# esp32-board.net
KiCad netlist of a schematic drawn in EasyEDA Pro
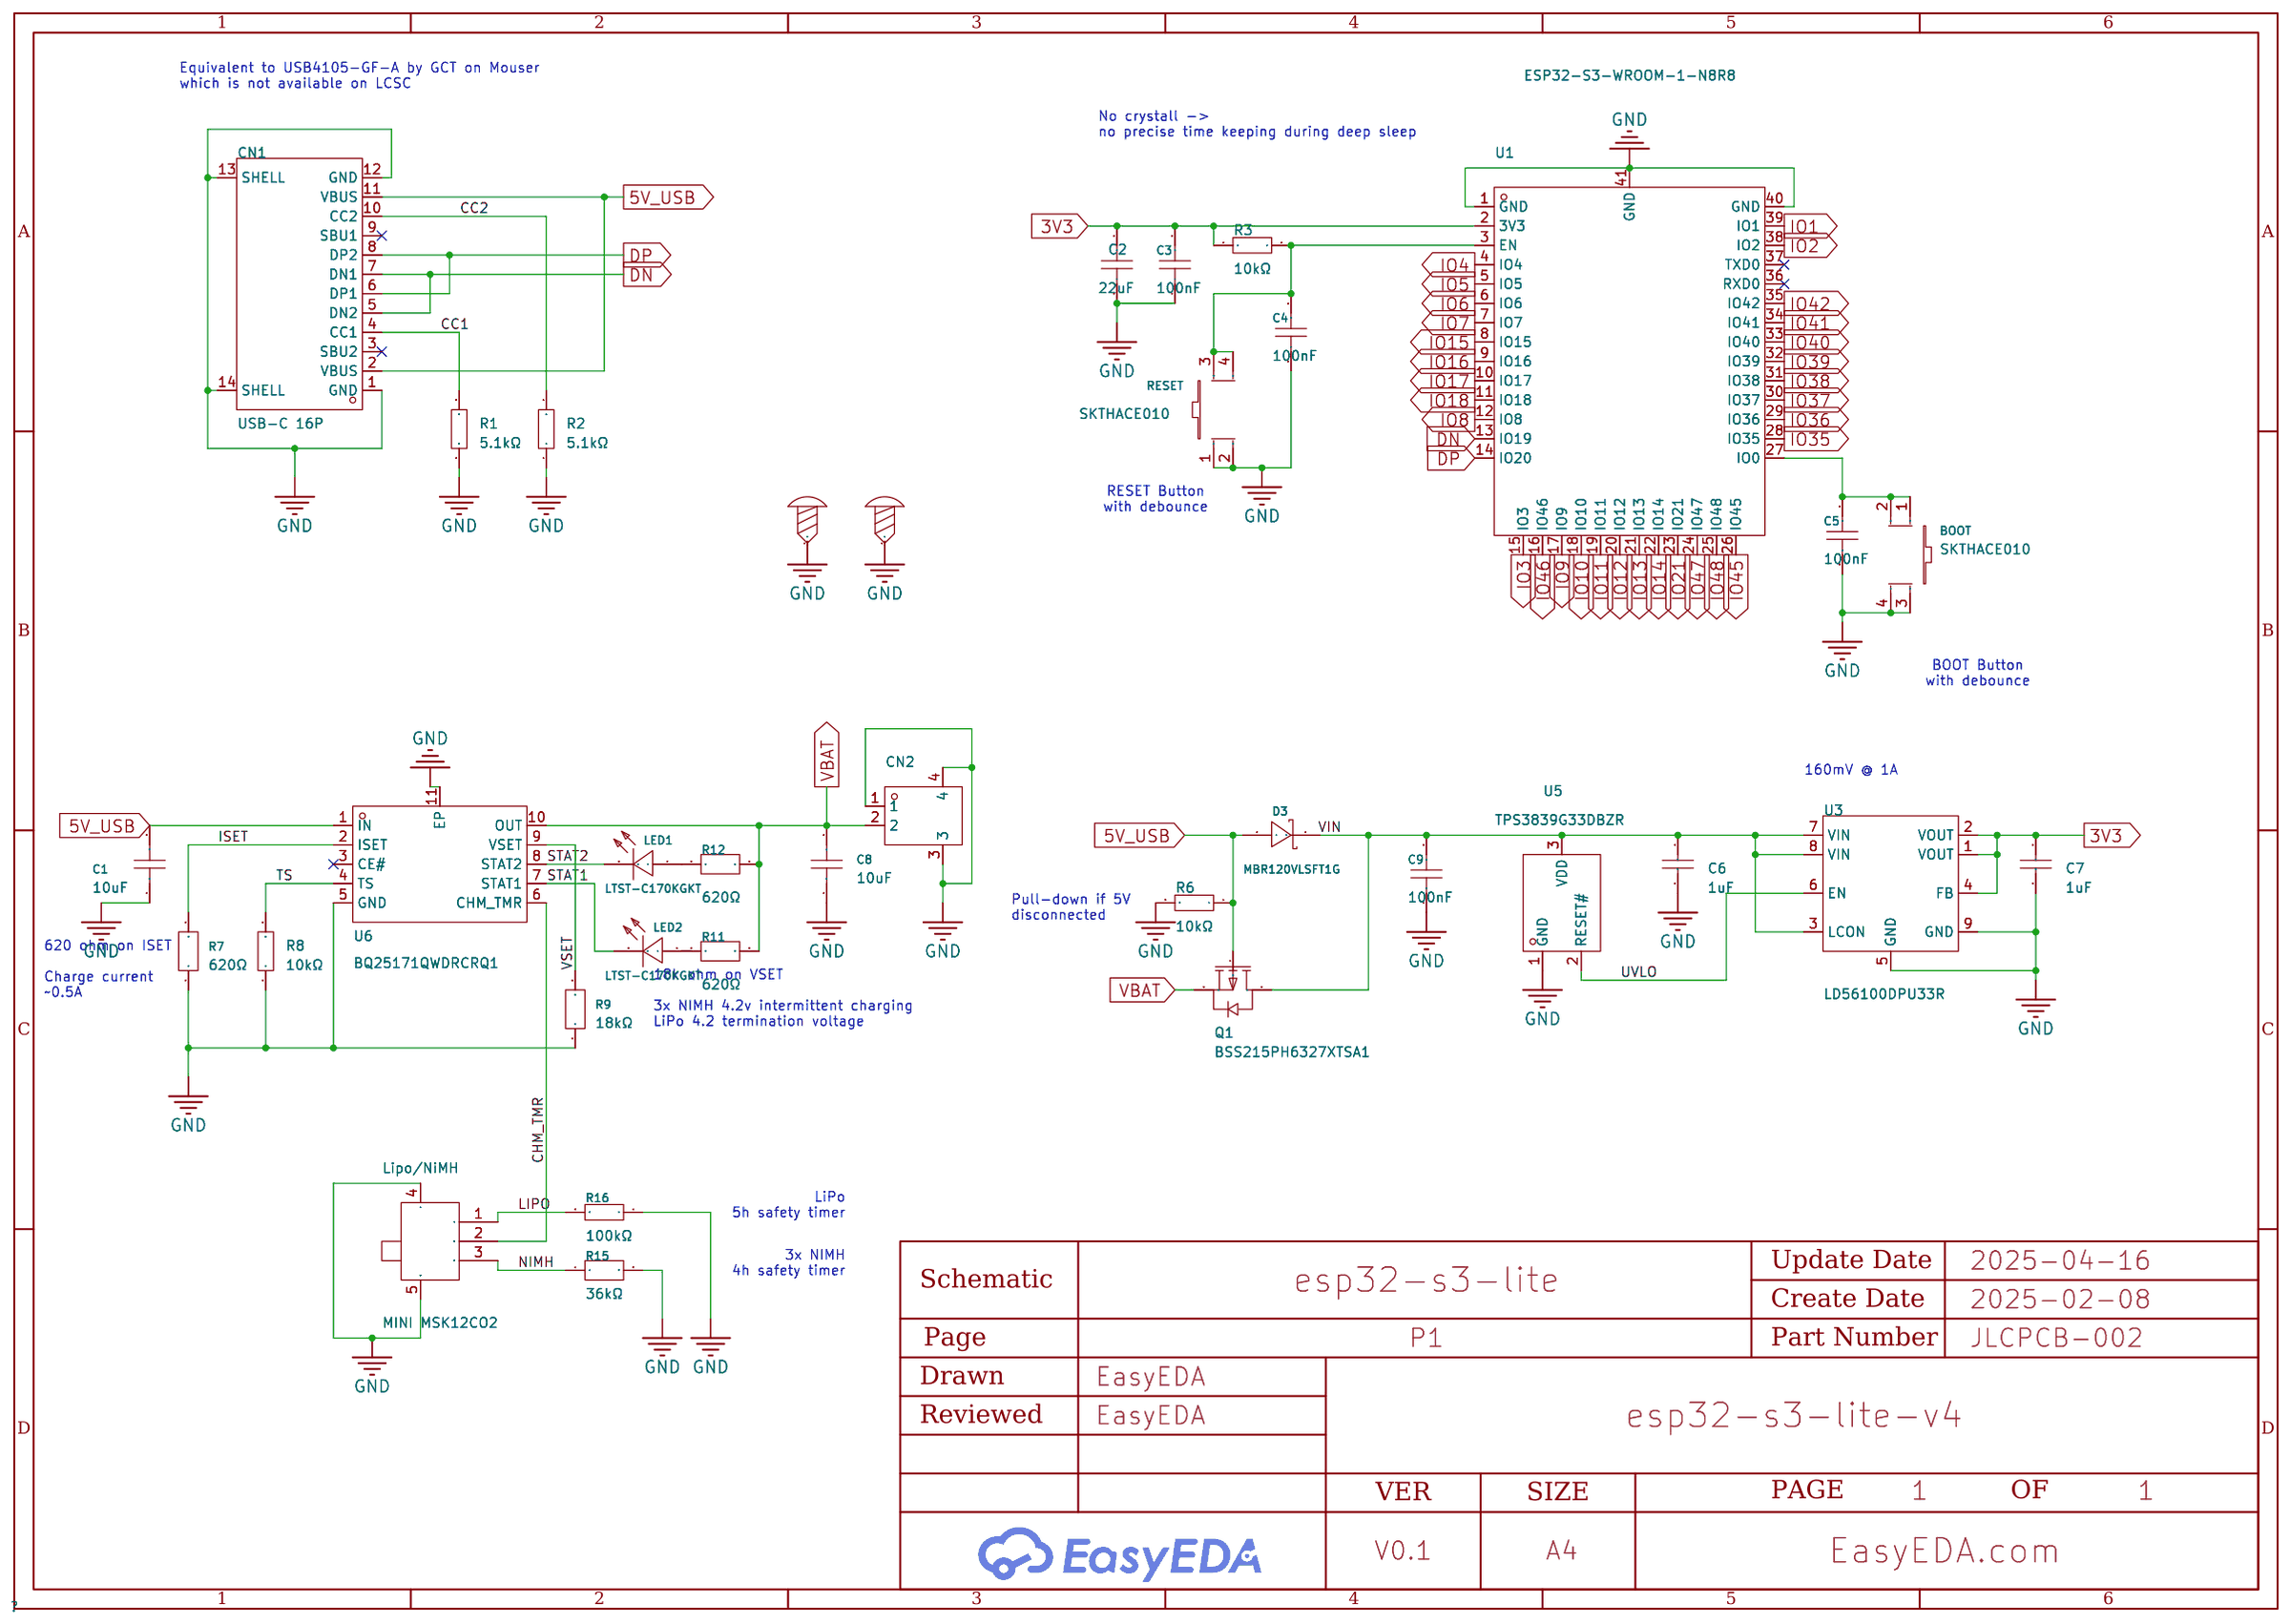
[diagram p0: schematic sheet]

(export (version "E")
  (design (tool "Eeschema 10.0.6"))
  (components
    (comp (ref "BOOT")
      (value "SKTHACE010")
      (footprint "easyedapro:KEY-SMD_4P-L3.5-W3.2-P1.50-LS3.60")
      (fields (field (name "Manufacturer") "ALPSALPINE(阿尔卑斯阿尔派)"))
      (libsource (lib "easyedapro") (part "SKTHACE010"))
    )
    (comp (ref "C1")
      (value "10uF")
      (footprint "easyedapro:C0603")
      (fields
        (field (name "Manufacturer Part") "CL10A106MA8NRNC")
        (field (name "Manufacturer") "SAMSUNG(三星)")
      )
      (libsource (lib "easyedapro") (part "CL10A106MA8NRNC"))
    )
    (comp (ref "C2")
      (value "22uF")
      (footprint "easyedapro:C0603")
      (fields
        (field (name "Manufacturer Part") "CL10A226MP8NUNE")
        (field (name "Manufacturer") "SAMSUNG(三星)")
      )
      (libsource (lib "easyedapro") (part "CL10A226MP8NUNE"))
    )
    (comp (ref "C3")
      (value "100nF")
      (footprint "easyedapro:C0603")
      (fields
        (field (name "Manufacturer Part") "CL10B104KB8NNNC")
        (field (name "Manufacturer") "SAMSUNG(三星)")
      )
      (libsource (lib "easyedapro") (part "CL10B104KB8NNNC"))
    )
    (comp (ref "C4")
      (value "100nF")
      (footprint "easyedapro:C0603")
      (fields
        (field (name "Manufacturer Part") "CL10B104KB8NNNC")
        (field (name "Manufacturer") "SAMSUNG(三星)")
      )
      (libsource (lib "easyedapro") (part "CL10B104KB8NNNC"))
    )
    (comp (ref "C5")
      (value "100nF")
      (footprint "easyedapro:C0603")
      (fields
        (field (name "Manufacturer Part") "CL10B104KB8NNNC")
        (field (name "Manufacturer") "SAMSUNG(三星)")
      )
      (libsource (lib "easyedapro") (part "CL10B104KB8NNNC"))
    )
    (comp (ref "C6")
      (value "1uF")
      (footprint "easyedapro:C0603")
      (fields
        (field (name "Manufacturer Part") "CL10A105KA8NNNC")
        (field (name "Manufacturer") "SAMSUNG(三星)")
      )
      (libsource (lib "easyedapro") (part "CL10A105KA8NNNC"))
    )
    (comp (ref "C7")
      (value "1uF")
      (footprint "easyedapro:C0603")
      (fields
        (field (name "Manufacturer Part") "CL10A105KA8NNNC")
        (field (name "Manufacturer") "SAMSUNG(三星)")
      )
      (libsource (lib "easyedapro") (part "CL10A105KA8NNNC"))
    )
    (comp (ref "C8")
      (value "10uF")
      (footprint "easyedapro:C0603")
      (fields
        (field (name "Manufacturer Part") "CL10A106MA8NRNC")
        (field (name "Manufacturer") "SAMSUNG(三星)")
      )
      (libsource (lib "easyedapro") (part "CL10A106MA8NRNC"))
    )
    (comp (ref "C9")
      (value "100nF")
      (footprint "easyedapro:C0603")
      (fields
        (field (name "Manufacturer Part") "CL10B104KB8NNNC")
        (field (name "Manufacturer") "SAMSUNG(三星)")
      )
      (libsource (lib "easyedapro") (part "CL10B104KB8NNNC"))
    )
    (comp (ref "CN1")
      (value "USB-C 16P")
      (footprint "easyedapro:USB-C-SMD_TYPE-C-6PIN-2MD-073")
      (fields
        (field (name "Manufacturer Part") "TYPE-C 16PIN 2MD(073)")
        (field (name "Manufacturer") "SHOU HAN(首韩)")
      )
      (libsource (lib "easyedapro") (part "TYPE-C 16PIN 2MD(073)"))
    )
    (comp (ref "CN2")
      (value "B2B-PH-SM4-TB(LF)(SN)")
      (footprint "easyedapro:CONN-SMD_B2B-PH-SM4-TB-LF-SN")
      (fields (field (name "Manufacturer") "JST"))
      (libsource (lib "easyedapro") (part "B2B-PH-SM4-TB (LF)(SN)"))
    )
    (comp (ref "D3")
      (value "MBR120VLSFT1G")
      (footprint "easyedapro:SOD-123F_L2.8-W1.8-LS3.7-RD")
      (fields (field (name "Manufacturer") "onsemi(安森美)"))
      (libsource (lib "easyedapro") (part "MBR120VLSFT1G"))
    )
    (comp (ref "LED1")
      (value "LTST-C170KGKT")
      (footprint "easyedapro:LED0805-R-RD")
      (fields (field (name "Manufacturer") "LITEON(光宝)"))
      (libsource (lib "easyedapro") (part "LTST-C170KGKT"))
    )
    (comp (ref "LED2")
      (value "LTST-C170KGKT")
      (footprint "easyedapro:LED0805-R-RD")
      (fields (field (name "Manufacturer") "LITEON(光宝)"))
      (libsource (lib "easyedapro") (part "LTST-C170KGKT"))
    )
    (comp (ref "Lipo/NiMH")
      (value "MINI MSK12CO2")
      (footprint "easyedapro:SW-SMD_MSK12CO2")
      (fields (field (name "Manufacturer") "SHOU HAN(首韩)"))
      (libsource (lib "easyedapro") (part "MINI MSK12CO2"))
    )
    (comp (ref "Q1")
      (value "BSS215PH6327XTSA1")
      (footprint "easyedapro:SOT-23-3_L2.9-W1.3-P1.90-LS2.4-BR")
      (fields (field (name "Manufacturer") "Infineon(英飞凌)"))
      (libsource (lib "easyedapro") (part "BSS215PH6327XTSA1"))
    )
    (comp (ref "R1")
      (value "5.1kΩ")
      (footprint "easyedapro:R0603")
      (fields (field (name "Manufacturer Part") "RT0603BRD075K1L") (field (name "Manufacturer") "YAGEO(国巨)"))
      (libsource (lib "easyedapro") (part "RT0603BRD075K1L"))
    )
    (comp (ref "R2")
      (value "5.1kΩ")
      (footprint "easyedapro:R0603")
      (fields (field (name "Manufacturer Part") "RT0603BRD075K1L") (field (name "Manufacturer") "YAGEO(国巨)"))
      (libsource (lib "easyedapro") (part "RT0603BRD075K1L"))
    )
    (comp (ref "R3")
      (value "10kΩ")
      (footprint "easyedapro:R0603")
      (fields (field (name "Manufacturer Part") "RT0603BRD0710KL") (field (name "Manufacturer") "YAGEO(国巨)"))
      (libsource (lib "easyedapro") (part "RT0603BRD0710KL"))
    )
    (comp (ref "R6")
      (value "10kΩ")
      (footprint "easyedapro:R0603")
      (fields (field (name "Manufacturer Part") "RT0603BRD0710KL") (field (name "Manufacturer") "YAGEO(国巨)"))
      (libsource (lib "easyedapro") (part "RT0603BRD0710KL"))
    )
    (comp (ref "R7")
      (value "620Ω")
      (footprint "easyedapro:R0603")
      (fields (field (name "Manufacturer Part") "ERJ3EKF6200V") (field (name "Manufacturer") "PANASONIC(松下)"))
      (libsource (lib "easyedapro") (part "ERJ3EKF6200V"))
    )
    (comp (ref "R8")
      (value "10kΩ")
      (footprint "easyedapro:R0603")
      (fields (field (name "Manufacturer Part") "RT0603BRD0710KL") (field (name "Manufacturer") "YAGEO(国巨)"))
      (libsource (lib "easyedapro") (part "RT0603BRD0710KL"))
    )
    (comp (ref "R9")
      (value "18kΩ")
      (footprint "easyedapro:R0603")
      (fields (field (name "Manufacturer Part") "ERJ3EKF1802V") (field (name "Manufacturer") "PANASONIC(松下)"))
      (libsource (lib "easyedapro") (part "ERJ3EKF1802V"))
    )
    (comp (ref "R11")
      (value "620Ω")
      (footprint "easyedapro:R0603")
      (fields (field (name "Manufacturer Part") "ERJ3EKF6200V") (field (name "Manufacturer") "PANASONIC(松下)"))
      (libsource (lib "easyedapro") (part "ERJ3EKF6200V"))
    )
    (comp (ref "R12")
      (value "620Ω")
      (footprint "easyedapro:R0603")
      (fields (field (name "Manufacturer Part") "ERJ3EKF6200V") (field (name "Manufacturer") "PANASONIC(松下)"))
      (libsource (lib "easyedapro") (part "ERJ3EKF6200V"))
    )
    (comp (ref "R15")
      (value "36kΩ")
      (footprint "easyedapro:R0603")
      (fields (field (name "Manufacturer Part") "ERJ3EKF3602V") (field (name "Manufacturer") "PANASONIC(松下)"))
      (libsource (lib "easyedapro") (part "ERJ3EKF3602V"))
    )
    (comp (ref "R16")
      (value "100kΩ")
      (footprint "easyedapro:R0603")
      (fields (field (name "Manufacturer Part") "ERJ3EKF1003V") (field (name "Manufacturer") "PANASONIC(松下)"))
      (libsource (lib "easyedapro") (part "ERJ3EKF1003V"))
    )
    (comp (ref "RESET")
      (value "SKTHACE010")
      (footprint "easyedapro:KEY-SMD_4P-L3.5-W3.2-P1.50-LS3.60")
      (fields (field (name "Manufacturer") "ALPSALPINE(阿尔卑斯阿尔派)"))
      (libsource (lib "easyedapro") (part "SKTHACE010"))
    )
    (comp (ref "SCREW1")
      (value "~")
      (footprint "easyedapro:Screw-Hole-M2")
      (libsource (lib "easyedapro") (part "Screw-Hole"))
    )
    (comp (ref "SCREW2")
      (value "~")
      (footprint "easyedapro:Screw-Hole-M2")
      (libsource (lib "easyedapro") (part "Screw-Hole"))
    )
    (comp (ref "U1")
      (value "ESP32-S3-WROOM-1-N8R8")
      (footprint "easyedapro:WIRELM-SMD_ESP32-S3-WROOM-1")
      (fields (field (name "Manufacturer") "ESPRESSIF(乐鑫)"))
      (libsource (lib "easyedapro") (part "ESP32-S3-WROOM-1(N8R8)"))
    )
    (comp (ref "U3")
      (value "LD56100DPU33R")
      (footprint "easyedapro:XDFN-8_L1.6-W1.2-P0.40-BL-EP")
      (fields (field (name "Manufacturer") "ST(意法半导体)"))
      (libsource (lib "easyedapro") (part "LD56100DPU33R"))
    )
    (comp (ref "U5")
      (value "TPS3839G33DBZR")
      (footprint "easyedapro:SOT-23-3_L2.9-W1.3-P1.90-LS2.4-BR")
      (fields (field (name "Manufacturer") "TI(德州仪器)"))
      (libsource (lib "easyedapro") (part "TPS3839G33DBZR"))
    )
    (comp (ref "U6")
      (value "BQ25171QWDRCRQ1")
      (footprint "easyedapro:VSON-10_L3.0-W3.0-P0.50-BL-EP1.65")
      (fields (field (name "Manufacturer") "TI(德州仪器)"))
      (libsource (lib "easyedapro") (part "BQ25171QWDRCRQ1"))
    )
  )
  (nets
    (net (code "1") (name "/CC1") (class "Default")
      (node (ref "CN1") (pin "4") (pinfunction "CC1_4") (pintype "unspecified"))
      (node (ref "R1") (pin "2") (pinfunction "2_2") (pintype "input"))
    )
    (net (code "2") (name "/CC2") (class "Default")
      (node (ref "CN1") (pin "10") (pinfunction "CC2_10") (pintype "unspecified"))
      (node (ref "R2") (pin "2") (pinfunction "2_2") (pintype "input"))
    )
    (net (code "3") (name "/CHM_TMR") (class "Default")
      (node (ref "Lipo/NiMH") (pin "2") (pinfunction "2_2") (pintype "unspecified"))
      (node (ref "U6") (pin "6") (pinfunction "CHM_TMR_6") (pintype "unspecified"))
    )
    (net (code "4") (name "/ISET") (class "Default")
      (node (ref "R7") (pin "2") (pinfunction "2_2") (pintype "input"))
      (node (ref "U6") (pin "2") (pinfunction "ISET_2") (pintype "unspecified"))
    )
    (net (code "5") (name "/LIPO") (class "Default")
      (node (ref "Lipo/NiMH") (pin "1") (pinfunction "1_1") (pintype "unspecified"))
      (node (ref "R16") (pin "2") (pinfunction "2_2") (pintype "input"))
    )
    (net (code "6") (name "/NIMH") (class "Default")
      (node (ref "Lipo/NiMH") (pin "3") (pinfunction "3_3") (pintype "unspecified"))
      (node (ref "R15") (pin "1") (pinfunction "1_1") (pintype "input"))
    )
    (net (code "7") (name "/STAT1") (class "Default")
      (node (ref "LED2") (pin "2") (pinfunction "K_2") (pintype "unspecified"))
      (node (ref "U6") (pin "7") (pinfunction "STAT1_7") (pintype "unspecified"))
    )
    (net (code "8") (name "/STAT2") (class "Default")
      (node (ref "LED1") (pin "2") (pinfunction "K_2") (pintype "unspecified"))
      (node (ref "U6") (pin "8") (pinfunction "STAT2_8") (pintype "unspecified"))
    )
    (net (code "9") (name "/TS") (class "Default")
      (node (ref "R8") (pin "2") (pinfunction "2_2") (pintype "input"))
      (node (ref "U6") (pin "4") (pinfunction "TS_4") (pintype "unspecified"))
    )
    (net (code "10") (name "/UVLO") (class "Default")
      (node (ref "U3") (pin "6") (pinfunction "EN_6") (pintype "unspecified"))
      (node (ref "U5") (pin "2") (pinfunction "RESET#_2") (pintype "input"))
    )
    (net (code "11") (name "/VIN") (class "Default")
      (node (ref "C6") (pin "2") (pinfunction "2_2") (pintype "input"))
      (node (ref "C9") (pin "2") (pinfunction "2_2") (pintype "input"))
      (node (ref "D3") (pin "1") (pinfunction "K_1") (pintype "input"))
      (node (ref "Q1") (pin "3") (pinfunction "D_3") (pintype "unspecified"))
      (node (ref "U3") (pin "3") (pinfunction "LCON_3") (pintype "unspecified"))
      (node (ref "U3") (pin "7") (pinfunction "VIN_7") (pintype "unspecified"))
      (node (ref "U3") (pin "8") (pinfunction "VIN_8") (pintype "unspecified"))
      (node (ref "U5") (pin "3") (pinfunction "VDD_3") (pintype "input"))
    )
    (net (code "12") (name "/VSET") (class "Default")
      (node (ref "R9") (pin "2") (pinfunction "2_2") (pintype "input"))
      (node (ref "U6") (pin "9") (pinfunction "VSET_9") (pintype "unspecified"))
    )
    (net (code "13") (name "3V3") (class "Default")
      (node (ref "C2") (pin "2") (pinfunction "2_2") (pintype "unspecified"))
      (node (ref "C3") (pin "2") (pinfunction "2_2") (pintype "input"))
      (node (ref "C7") (pin "2") (pinfunction "2_2") (pintype "input"))
      (node (ref "R3") (pin "1") (pinfunction "1_1") (pintype "input"))
      (node (ref "U1") (pin "2") (pinfunction "3V3_2") (pintype "unspecified"))
      (node (ref "U3") (pin "1") (pinfunction "VOUT_1") (pintype "unspecified"))
      (node (ref "U3") (pin "2") (pinfunction "VOUT_2") (pintype "unspecified"))
      (node (ref "U3") (pin "4") (pinfunction "FB_4") (pintype "unspecified"))
    )
    (net (code "14") (name "5V_USB") (class "Default")
      (node (ref "C1") (pin "2") (pinfunction "2_2") (pintype "input"))
      (node (ref "CN1") (pin "11") (pinfunction "VBUS_11") (pintype "unspecified"))
      (node (ref "CN1") (pin "2") (pinfunction "VBUS_2") (pintype "unspecified"))
      (node (ref "D3") (pin "2") (pinfunction "A_2") (pintype "input"))
      (node (ref "Q1") (pin "1") (pinfunction "G_1") (pintype "unspecified"))
      (node (ref "R6") (pin "1") (pinfunction "1_1") (pintype "input"))
      (node (ref "U6") (pin "1") (pinfunction "IN_1") (pintype "unspecified"))
    )
    (net (code "15") (name "DN") (class "Default")
      (node (ref "CN1") (pin "5") (pinfunction "DN2_5") (pintype "unspecified"))
      (node (ref "CN1") (pin "7") (pinfunction "DN1_7") (pintype "unspecified"))
      (node (ref "U1") (pin "13") (pinfunction "IO19_13") (pintype "unspecified"))
    )
    (net (code "16") (name "DP") (class "Default")
      (node (ref "CN1") (pin "6") (pinfunction "DP1_6") (pintype "unspecified"))
      (node (ref "CN1") (pin "8") (pinfunction "DP2_8") (pintype "unspecified"))
      (node (ref "U1") (pin "14") (pinfunction "IO20_14") (pintype "unspecified"))
    )
    (net (code "17") (name "GND") (class "Default")
      (node (ref "BOOT") (pin "3") (pinfunction "3_3") (pintype "input"))
      (node (ref "BOOT") (pin "4") (pinfunction "4_4") (pintype "input"))
      (node (ref "C1") (pin "1") (pinfunction "1_1") (pintype "input"))
      (node (ref "C2") (pin "1") (pinfunction "1_1") (pintype "unspecified"))
      (node (ref "C3") (pin "1") (pinfunction "1_1") (pintype "input"))
      (node (ref "C4") (pin "1") (pinfunction "1_1") (pintype "input"))
      (node (ref "C5") (pin "1") (pinfunction "1_1") (pintype "input"))
      (node (ref "C6") (pin "1") (pinfunction "1_1") (pintype "input"))
      (node (ref "C7") (pin "1") (pinfunction "1_1") (pintype "input"))
      (node (ref "C8") (pin "1") (pinfunction "1_1") (pintype "input"))
      (node (ref "C9") (pin "1") (pinfunction "1_1") (pintype "input"))
      (node (ref "CN1") (pin "1") (pinfunction "GND_1") (pintype "unspecified"))
      (node (ref "CN1") (pin "12") (pinfunction "GND_12") (pintype "unspecified"))
      (node (ref "CN1") (pin "13") (pinfunction "SHELL_13") (pintype "unspecified"))
      (node (ref "CN1") (pin "14") (pinfunction "SHELL_14") (pintype "unspecified"))
      (node (ref "CN2") (pin "1") (pinfunction "1_1") (pintype "unspecified"))
      (node (ref "CN2") (pin "3") (pinfunction "3_3") (pintype "unspecified"))
      (node (ref "CN2") (pin "4") (pinfunction "4_4") (pintype "unspecified"))
      (node (ref "Lipo/NiMH") (pin "4") (pinfunction "4_4") (pintype "unspecified"))
      (node (ref "Lipo/NiMH") (pin "5") (pinfunction "5_5") (pintype "unspecified"))
      (node (ref "R1") (pin "1") (pinfunction "1_1") (pintype "input"))
      (node (ref "R15") (pin "2") (pinfunction "2_2") (pintype "input"))
      (node (ref "R16") (pin "1") (pinfunction "1_1") (pintype "input"))
      (node (ref "R2") (pin "1") (pinfunction "1_1") (pintype "input"))
      (node (ref "R6") (pin "2") (pinfunction "2_2") (pintype "input"))
      (node (ref "R7") (pin "1") (pinfunction "1_1") (pintype "input"))
      (node (ref "R8") (pin "1") (pinfunction "1_1") (pintype "input"))
      (node (ref "R9") (pin "1") (pinfunction "1_1") (pintype "input"))
      (node (ref "RESET") (pin "1") (pinfunction "1_1") (pintype "input"))
      (node (ref "RESET") (pin "2") (pinfunction "2_2") (pintype "input"))
      (node (ref "SCREW1") (pin "1") (pinfunction "1_1") (pintype "input"))
      (node (ref "SCREW2") (pin "1") (pinfunction "1_1") (pintype "input"))
      (node (ref "U1") (pin "1") (pinfunction "GND_1") (pintype "unspecified"))
      (node (ref "U1") (pin "40") (pinfunction "GND_40") (pintype "unspecified"))
      (node (ref "U1") (pin "41") (pinfunction "GND_41") (pintype "unspecified"))
      (node (ref "U3") (pin "5") (pinfunction "GND_5") (pintype "unspecified"))
      (node (ref "U3") (pin "9") (pinfunction "GND_9") (pintype "unspecified"))
      (node (ref "U5") (pin "1") (pinfunction "GND_1") (pintype "input"))
      (node (ref "U6") (pin "11") (pinfunction "EP_11") (pintype "unspecified"))
      (node (ref "U6") (pin "5") (pinfunction "GND_5") (pintype "unspecified"))
    )
    (net (code "18") (name "IO1") (class "Default")
      (node (ref "U1") (pin "39") (pinfunction "IO1_39") (pintype "unspecified"))
    )
    (net (code "19") (name "IO2") (class "Default")
      (node (ref "U1") (pin "38") (pinfunction "IO2_38") (pintype "unspecified"))
    )
    (net (code "20") (name "IO3") (class "Default")
      (node (ref "U1") (pin "15") (pinfunction "IO3_15") (pintype "unspecified"))
    )
    (net (code "21") (name "IO4") (class "Default")
      (node (ref "U1") (pin "4") (pinfunction "IO4_4") (pintype "unspecified"))
    )
    (net (code "22") (name "IO5") (class "Default")
      (node (ref "U1") (pin "5") (pinfunction "IO5_5") (pintype "unspecified"))
    )
    (net (code "23") (name "IO6") (class "Default")
      (node (ref "U1") (pin "6") (pinfunction "IO6_6") (pintype "unspecified"))
    )
    (net (code "24") (name "IO7") (class "Default")
      (node (ref "U1") (pin "7") (pinfunction "IO7_7") (pintype "unspecified"))
    )
    (net (code "25") (name "IO8") (class "Default")
      (node (ref "U1") (pin "12") (pinfunction "IO8_12") (pintype "unspecified"))
    )
    (net (code "26") (name "IO9") (class "Default")
      (node (ref "U1") (pin "17") (pinfunction "IO9_17") (pintype "unspecified"))
    )
    (net (code "27") (name "IO10") (class "Default")
      (node (ref "U1") (pin "18") (pinfunction "IO10_18") (pintype "unspecified"))
    )
    (net (code "28") (name "IO11") (class "Default")
      (node (ref "U1") (pin "19") (pinfunction "IO11_19") (pintype "unspecified"))
    )
    (net (code "29") (name "IO12") (class "Default")
      (node (ref "U1") (pin "20") (pinfunction "IO12_20") (pintype "unspecified"))
    )
    (net (code "30") (name "IO13") (class "Default")
      (node (ref "U1") (pin "21") (pinfunction "IO13_21") (pintype "unspecified"))
    )
    (net (code "31") (name "IO14") (class "Default")
      (node (ref "U1") (pin "22") (pinfunction "IO14_22") (pintype "unspecified"))
    )
    (net (code "32") (name "IO15") (class "Default")
      (node (ref "U1") (pin "8") (pinfunction "IO15_8") (pintype "unspecified"))
    )
    (net (code "33") (name "IO16") (class "Default")
      (node (ref "U1") (pin "9") (pinfunction "IO16_9") (pintype "unspecified"))
    )
    (net (code "34") (name "IO17") (class "Default")
      (node (ref "U1") (pin "10") (pinfunction "IO17_10") (pintype "unspecified"))
    )
    (net (code "35") (name "IO18") (class "Default")
      (node (ref "U1") (pin "11") (pinfunction "IO18_11") (pintype "unspecified"))
    )
    (net (code "36") (name "IO21") (class "Default")
      (node (ref "U1") (pin "23") (pinfunction "IO21_23") (pintype "unspecified"))
    )
    (net (code "37") (name "IO35") (class "Default")
      (node (ref "U1") (pin "28") (pinfunction "IO35_28") (pintype "unspecified"))
    )
    (net (code "38") (name "IO36") (class "Default")
      (node (ref "U1") (pin "29") (pinfunction "IO36_29") (pintype "unspecified"))
    )
    (net (code "39") (name "IO37") (class "Default")
      (node (ref "U1") (pin "30") (pinfunction "IO37_30") (pintype "unspecified"))
    )
    (net (code "40") (name "IO38") (class "Default")
      (node (ref "U1") (pin "31") (pinfunction "IO38_31") (pintype "unspecified"))
    )
    (net (code "41") (name "IO39") (class "Default")
      (node (ref "U1") (pin "32") (pinfunction "IO39_32") (pintype "unspecified"))
    )
    (net (code "42") (name "IO40") (class "Default")
      (node (ref "U1") (pin "33") (pinfunction "IO40_33") (pintype "unspecified"))
    )
    (net (code "43") (name "IO41") (class "Default")
      (node (ref "U1") (pin "34") (pinfunction "IO41_34") (pintype "unspecified"))
    )
    (net (code "44") (name "IO42") (class "Default")
      (node (ref "U1") (pin "35") (pinfunction "IO42_35") (pintype "unspecified"))
    )
    (net (code "45") (name "IO45") (class "Default")
      (node (ref "U1") (pin "26") (pinfunction "IO45_26") (pintype "unspecified"))
    )
    (net (code "46") (name "IO46") (class "Default")
      (node (ref "U1") (pin "16") (pinfunction "IO46_16") (pintype "unspecified"))
    )
    (net (code "47") (name "IO47") (class "Default")
      (node (ref "U1") (pin "24") (pinfunction "IO47_24") (pintype "unspecified"))
    )
    (net (code "48") (name "IO48") (class "Default")
      (node (ref "U1") (pin "25") (pinfunction "IO48_25") (pintype "unspecified"))
    )
    (net (code "49") (name "Net-(LED1-A)") (class "Default")
      (node (ref "LED1") (pin "1") (pinfunction "A_1") (pintype "unspecified"))
      (node (ref "R12") (pin "1") (pinfunction "1_1") (pintype "input"))
    )
    (net (code "50") (name "Net-(LED2-A)") (class "Default")
      (node (ref "LED2") (pin "1") (pinfunction "A_1") (pintype "unspecified"))
      (node (ref "R11") (pin "1") (pinfunction "1_1") (pintype "input"))
    )
    (net (code "51") (name "Net-(U1-EN)") (class "Default")
      (node (ref "C4") (pin "2") (pinfunction "2_2") (pintype "input"))
      (node (ref "R3") (pin "2") (pinfunction "2_2") (pintype "input"))
      (node (ref "RESET") (pin "3") (pinfunction "3_3") (pintype "input"))
      (node (ref "RESET") (pin "4") (pinfunction "4_4") (pintype "input"))
      (node (ref "U1") (pin "3") (pinfunction "EN_3") (pintype "unspecified"))
    )
    (net (code "52") (name "Net-(U1-IO0)") (class "Default")
      (node (ref "BOOT") (pin "1") (pinfunction "1_1") (pintype "input"))
      (node (ref "BOOT") (pin "2") (pinfunction "2_2") (pintype "input"))
      (node (ref "C5") (pin "2") (pinfunction "2_2") (pintype "input"))
      (node (ref "U1") (pin "27") (pinfunction "IO0_27") (pintype "unspecified"))
    )
    (net (code "53") (name "VBAT") (class "Default")
      (node (ref "C8") (pin "2") (pinfunction "2_2") (pintype "input"))
      (node (ref "CN2") (pin "2") (pinfunction "2_2") (pintype "unspecified"))
      (node (ref "Q1") (pin "2") (pinfunction "S_2") (pintype "unspecified"))
      (node (ref "R11") (pin "2") (pinfunction "2_2") (pintype "input"))
      (node (ref "R12") (pin "2") (pinfunction "2_2") (pintype "input"))
      (node (ref "U6") (pin "10") (pinfunction "OUT_10") (pintype "unspecified"))
    )
    (net (code "54") (name "unconnected-(CN1-SBU1-Pad9)") (class "Default")
      (node (ref "CN1") (pin "9") (pinfunction "SBU1_9") (pintype "unspecified+no_connect"))
    )
    (net (code "55") (name "unconnected-(CN1-SBU2-Pad3)") (class "Default")
      (node (ref "CN1") (pin "3") (pinfunction "SBU2_3") (pintype "unspecified+no_connect"))
    )
    (net (code "56") (name "unconnected-(U1-RXD0-Pad36)") (class "Default")
      (node (ref "U1") (pin "36") (pinfunction "RXD0_36") (pintype "unspecified+no_connect"))
    )
    (net (code "57") (name "unconnected-(U1-TXD0-Pad37)") (class "Default")
      (node (ref "U1") (pin "37") (pinfunction "TXD0_37") (pintype "unspecified+no_connect"))
    )
    (net (code "58") (name "unconnected-(U6-CE#-Pad3)") (class "Default")
      (node (ref "U6") (pin "3") (pinfunction "CE#_3") (pintype "unspecified+no_connect"))
    )
  )
)
